# Current_Limit.net
KiCad netlist of a schematic drawn in Altium Designer
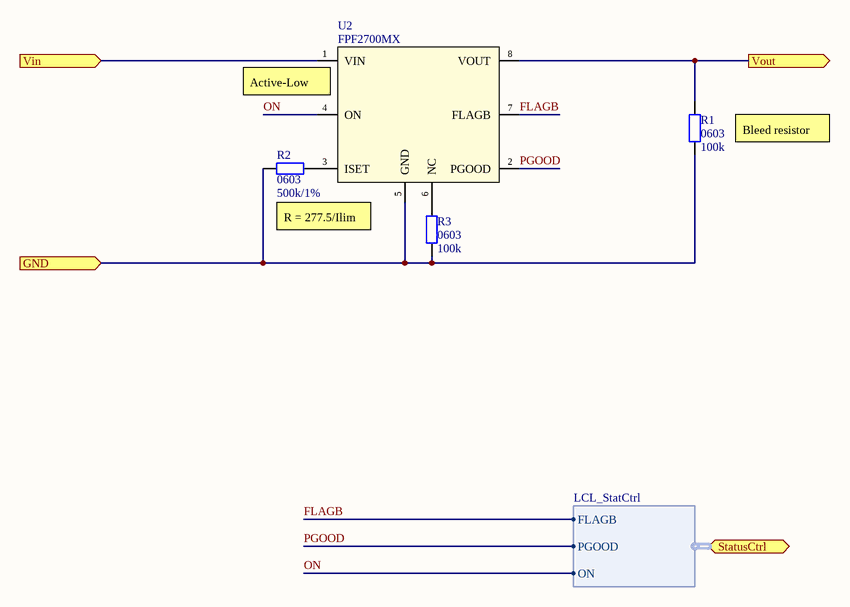
[diagram p0: Current_Limit.SchDoc]

(export (version "E")
  (design (tool "Eeschema 10.0.6"))
  (components
    (comp (ref "R1")
      (value "0603")
      (footprint "SMD_Resistor_0603")
      (description "Resistor")
      (fields (field (name "ALTIUM_VALUE") "100k") (field (name "PUBLISHER") "Altium Limited"))
      (libsource (lib "") (part "Res2_1"))
    )
    (comp (ref "R2")
      (value "0603")
      (footprint "SMD_Resistor_0603")
      (description "Resistor")
      (fields (field (name "ALTIUM_VALUE") "500k/1%") (field (name "PUBLISHER") "Altium Limited"))
      (libsource (lib "Miscellaneous Devices") (part "Res2"))
    )
    (comp (ref "R3")
      (value "0603")
      (footprint "SMD_Resistor_0603")
      (description "Resistor")
      (fields (field (name "ALTIUM_VALUE") "100k") (field (name "PUBLISHER") "Altium Limited"))
      (libsource (lib "") (part "Res2_1"))
    )
    (comp (ref "U2")
      (value "FPF2700MX")
      (footprint "SOIC-8-N")
      (description "Adj over-current protection 0.4-2A, Load Switch")
      (fields (field (name "MANUFACTURER") "Fairchild Semiconductor"))
      (libsource (lib "microcircuits_other-functions") (part "FPF2700MX"))
    )
  )
  (nets
    (net (code "2") (name "/FLAGB") (class "Default")
      (node (ref "U2") (pin "7") (pinfunction "FLAGB_7") (pintype "passive"))
    )
    (net (code "3") (name "/GND") (class "Default")
      (node (ref "R1") (pin "2") (pinfunction "2_2") (pintype "passive"))
      (node (ref "R2") (pin "1") (pinfunction "1_1") (pintype "passive"))
      (node (ref "R3") (pin "2") (pinfunction "2_2") (pintype "passive"))
      (node (ref "U2") (pin "5") (pinfunction "GND_5") (pintype "passive"))
    )
    (net (code "4") (name "/ON") (class "Default")
      (node (ref "U2") (pin "4") (pinfunction "ON_4") (pintype "passive"))
    )
    (net (code "5") (name "/PGOOD") (class "Default")
      (node (ref "U2") (pin "2") (pinfunction "PGOOD_2") (pintype "passive"))
    )
    (net (code "6") (name "/Vin") (class "Default")
      (node (ref "U2") (pin "1") (pinfunction "VIN_1") (pintype "passive"))
    )
    (net (code "7") (name "/Vout") (class "Default")
      (node (ref "R1") (pin "1") (pinfunction "1_1") (pintype "passive"))
      (node (ref "U2") (pin "8") (pinfunction "VOUT_8") (pintype "passive"))
    )
    (net (code "9") (name "Net-(U2-ISET)") (class "Default")
      (node (ref "R2") (pin "2") (pinfunction "2_2") (pintype "passive"))
      (node (ref "U2") (pin "3") (pinfunction "ISET_3") (pintype "passive"))
    )
    (net (code "10") (name "Net-(U2-NC)") (class "Default")
      (node (ref "R3") (pin "1") (pinfunction "1_1") (pintype "passive"))
      (node (ref "U2") (pin "6") (pinfunction "NC_6") (pintype "passive"))
    )
  )
)
